# MCU-Power.net
KiCad netlist of a schematic drawn in Altium Designer
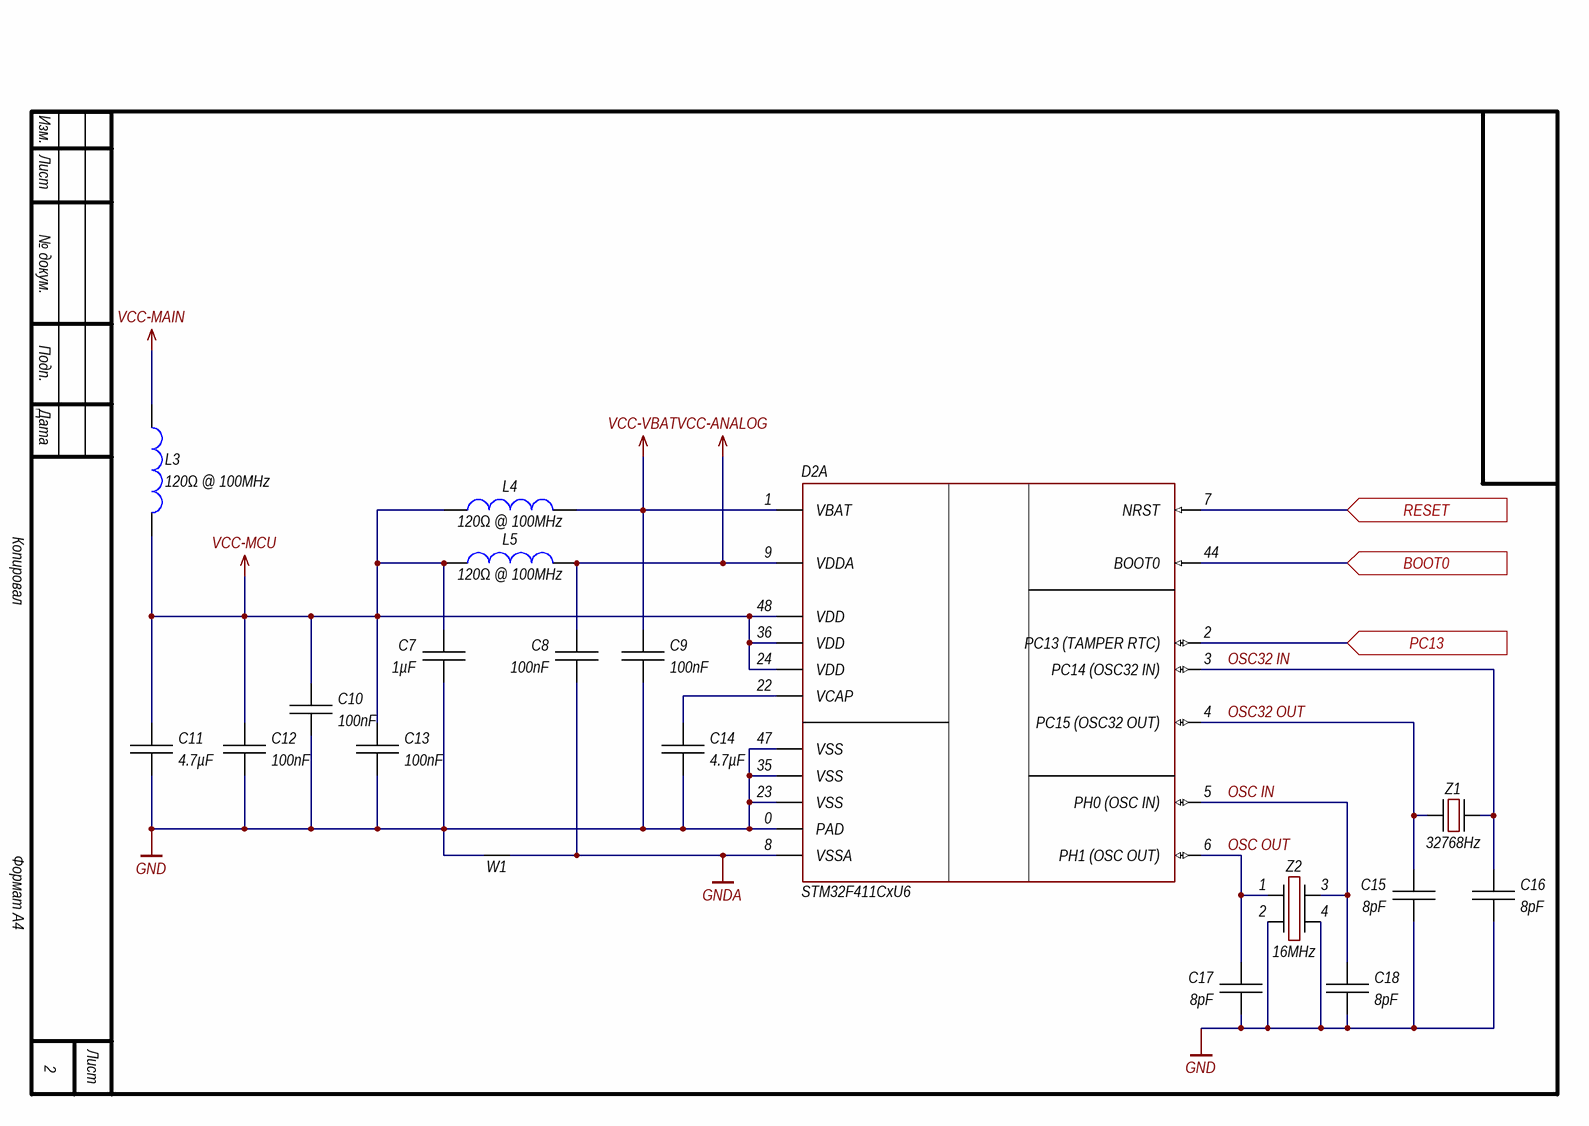
[diagram p0: MCU-Power.SchDoc]

(export (version "E")
  (design (tool "Eeschema 10.0.6"))
  (components
    (comp (ref "C7") (value "1µF") (footprint "CH0402C") (libsource (lib "Discrete") (part "Capacitor")))
    (comp (ref "C8") (value "100nF") (footprint "CH0402C") (libsource (lib "Discrete") (part "Capacitor")))
    (comp (ref "C9") (value "100nF") (footprint "CH0402C") (libsource (lib "Discrete") (part "Capacitor")))
    (comp (ref "C10") (value "100nF") (footprint "CH0402C") (libsource (lib "Discrete") (part "Capacitor")))
    (comp (ref "C11") (value "4.7µF") (footprint "CH0402C") (libsource (lib "Discrete") (part "Capacitor")))
    (comp (ref "C12") (value "100nF") (footprint "CH0402C") (libsource (lib "Discrete") (part "Capacitor")))
    (comp (ref "C13") (value "100nF") (footprint "CH0402C") (libsource (lib "Discrete") (part "Capacitor")))
    (comp (ref "C14") (value "4.7µF") (footprint "CH0402C") (libsource (lib "Discrete") (part "Capacitor")))
    (comp (ref "C15") (value "8pF") (footprint "CH0402C") (libsource (lib "Discrete") (part "Capacitor")))
    (comp (ref "C16") (value "8pF") (footprint "CH0402C") (libsource (lib "Discrete") (part "Capacitor")))
    (comp (ref "C17") (value "8pF") (footprint "CH0402C") (libsource (lib "Discrete") (part "Capacitor")))
    (comp (ref "C18") (value "8pF") (footprint "CH0402C") (libsource (lib "Discrete") (part "Capacitor")))
    (comp (ref "D2")
      (value "STM32F411CxU6")
      (footprint "48-UFQFPN")
      (description "STM32, Cortex-M4")
      (fields (field (name "MANUFACTURER") "ST Microelectronics"))
      (libsource (lib "Digital") (part "STM32F411CxU6"))
    )
    (comp (ref "L3")
      (value "120Ω @ 100MHz")
      (footprint "CH0402L")
      (libsource (lib "Discrete") (part "Inductor"))
    )
    (comp (ref "L4")
      (value "120Ω @ 100MHz")
      (footprint "CH0402L")
      (libsource (lib "Discrete") (part "Inductor"))
    )
    (comp (ref "L5")
      (value "120Ω @ 100MHz")
      (footprint "CH0402L")
      (libsource (lib "Discrete") (part "Inductor"))
    )
    (comp (ref "W1")
      (value "Net Tie")
      (footprint "CON: Net Tie 1.1x0.5")
      (libsource (lib "Connectors") (part "Net Tie"))
    )
    (comp (ref "Z1")
      (value "32768Hz")
      (footprint "OSC: 2012")
      (libsource (lib "Discrete") (part "Oscillator"))
    )
    (comp (ref "Z2") (value "16MHz") (footprint "OSC: 2520") (libsource (lib "Discrete") (part "Generator")))
  )
  (nets
    (net (code "1") (name "/BOOT0") (class "Default")
      (node (ref "D2") (pin "44") (pinfunction "BOOT0_44") (pintype "input"))
    )
    (net (code "2") (name "/OSC IN") (class "Default")
      (node (ref "C18") (pin "2") (pinfunction "2_2") (pintype "passive"))
      (node (ref "D2") (pin "5") (pinfunction "PH0_(OSC_IN)_5") (pintype "bidirectional"))
      (node (ref "Z2") (pin "3") (pinfunction "3_3") (pintype "passive"))
    )
    (net (code "3") (name "/OSC OUT") (class "Default")
      (node (ref "C17") (pin "2") (pinfunction "2_2") (pintype "passive"))
      (node (ref "D2") (pin "6") (pinfunction "PH1_(OSC_OUT)_6") (pintype "bidirectional"))
      (node (ref "Z2") (pin "1") (pinfunction "1_1") (pintype "passive"))
    )
    (net (code "4") (name "/OSC32 IN") (class "Default")
      (node (ref "C16") (pin "2") (pinfunction "2_2") (pintype "passive"))
      (node (ref "D2") (pin "3") (pinfunction "PC14_(OSC32_IN)_3") (pintype "bidirectional"))
      (node (ref "Z1") (pin "3") (pinfunction "3_3") (pintype "passive"))
    )
    (net (code "5") (name "/OSC32 OUT") (class "Default")
      (node (ref "C15") (pin "2") (pinfunction "2_2") (pintype "passive"))
      (node (ref "D2") (pin "4") (pinfunction "PC15_(OSC32_OUT)_4") (pintype "bidirectional"))
      (node (ref "Z1") (pin "1") (pinfunction "1_1") (pintype "passive"))
    )
    (net (code "6") (name "/PC13") (class "Default")
      (node (ref "D2") (pin "2") (pinfunction "PC13_(TAMPER_RTC)_2") (pintype "bidirectional"))
    )
    (net (code "7") (name "/RESET") (class "Default")
      (node (ref "D2") (pin "7") (pinfunction "NRST_7") (pintype "input"))
    )
    (net (code "8") (name "GND") (class "Default")
      (node (ref "C10") (pin "1") (pinfunction "1_1") (pintype "passive"))
      (node (ref "C11") (pin "1") (pinfunction "1_1") (pintype "passive"))
      (node (ref "C12") (pin "1") (pinfunction "1_1") (pintype "passive"))
      (node (ref "C13") (pin "1") (pinfunction "1_1") (pintype "passive"))
      (node (ref "C14") (pin "1") (pinfunction "1_1") (pintype "passive"))
      (node (ref "C15") (pin "1") (pinfunction "1_1") (pintype "passive"))
      (node (ref "C16") (pin "1") (pinfunction "1_1") (pintype "passive"))
      (node (ref "C17") (pin "1") (pinfunction "1_1") (pintype "passive"))
      (node (ref "C18") (pin "1") (pinfunction "1_1") (pintype "passive"))
      (node (ref "C7") (pin "1") (pinfunction "1_1") (pintype "passive"))
      (node (ref "C9") (pin "1") (pinfunction "1_1") (pintype "passive"))
      (node (ref "D2") (pin "0") (pinfunction "PAD_0") (pintype "power_in"))
      (node (ref "D2") (pin "23") (pinfunction "VSS_23") (pintype "power_in"))
      (node (ref "D2") (pin "35") (pinfunction "VSS_35") (pintype "power_in"))
      (node (ref "D2") (pin "47") (pinfunction "VSS_47") (pintype "power_in"))
      (node (ref "W1") (pin "1") (pinfunction "1_1") (pintype "power_in"))
      (node (ref "Z2") (pin "2") (pinfunction "2_2") (pintype "passive"))
      (node (ref "Z2") (pin "4") (pinfunction "4_4") (pintype "passive"))
    )
    (net (code "9") (name "GNDA") (class "Default")
      (node (ref "C8") (pin "1") (pinfunction "1_1") (pintype "passive"))
      (node (ref "D2") (pin "8") (pinfunction "VSSA_8") (pintype "power_in"))
      (node (ref "W1") (pin "2") (pinfunction "2_2") (pintype "power_in"))
    )
    (net (code "10") (name "Net-(D2A-VCAP)") (class "Default")
      (node (ref "C14") (pin "2") (pinfunction "2_2") (pintype "passive"))
      (node (ref "D2") (pin "22") (pinfunction "VCAP_22") (pintype "power_in"))
    )
    (net (code "11") (name "VCC-ANALOG") (class "Default")
      (node (ref "C8") (pin "2") (pinfunction "2_2") (pintype "passive"))
      (node (ref "D2") (pin "9") (pinfunction "VDDA_9") (pintype "power_in"))
      (node (ref "L5") (pin "1") (pinfunction "1_1") (pintype "passive"))
    )
    (net (code "12") (name "VCC-MAIN") (class "Default")
      (node (ref "L3") (pin "2") (pinfunction "2_2") (pintype "passive"))
    )
    (net (code "13") (name "VCC-MCU") (class "Default")
      (node (ref "C10") (pin "2") (pinfunction "2_2") (pintype "passive"))
      (node (ref "C11") (pin "2") (pinfunction "2_2") (pintype "passive"))
      (node (ref "C12") (pin "2") (pinfunction "2_2") (pintype "passive"))
      (node (ref "C13") (pin "2") (pinfunction "2_2") (pintype "passive"))
      (node (ref "C7") (pin "2") (pinfunction "2_2") (pintype "passive"))
      (node (ref "D2") (pin "24") (pinfunction "VDD_24") (pintype "power_in"))
      (node (ref "D2") (pin "36") (pinfunction "VDD_36") (pintype "power_in"))
      (node (ref "D2") (pin "48") (pinfunction "VDD_48") (pintype "power_in"))
      (node (ref "L3") (pin "1") (pinfunction "1_1") (pintype "passive"))
      (node (ref "L4") (pin "2") (pinfunction "2_2") (pintype "passive"))
      (node (ref "L5") (pin "2") (pinfunction "2_2") (pintype "passive"))
    )
    (net (code "14") (name "VCC-VBAT") (class "Default")
      (node (ref "C9") (pin "2") (pinfunction "2_2") (pintype "passive"))
      (node (ref "D2") (pin "1") (pinfunction "VBAT_1") (pintype "power_in"))
      (node (ref "L4") (pin "1") (pinfunction "1_1") (pintype "passive"))
    )
  )
)
